# micromouse_schematic.net
KiCad netlist of a schematic drawn in EAGLE
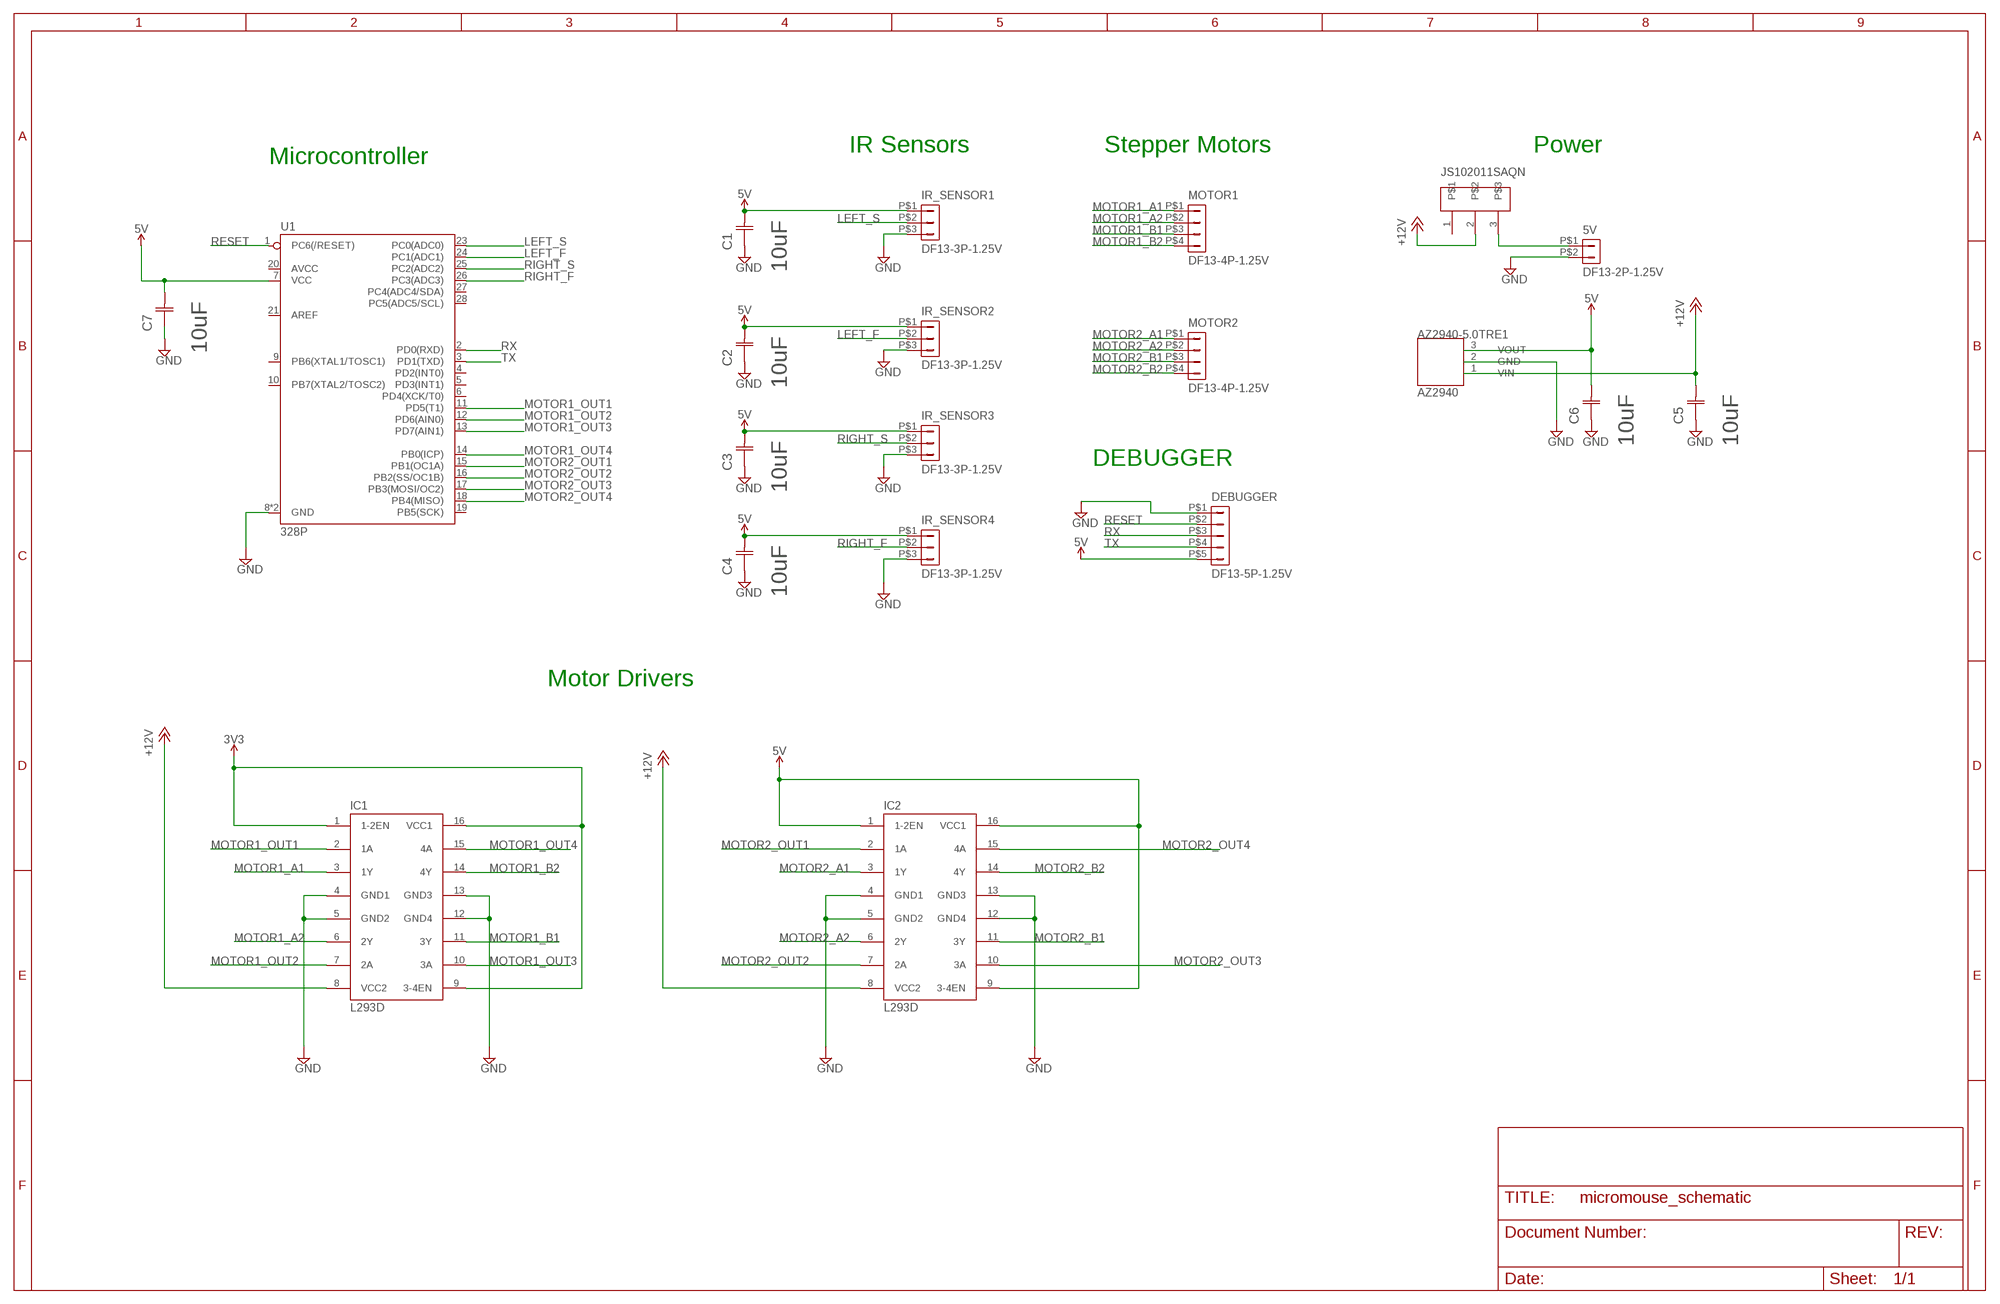
[diagram p0: schematic, sheet 1]

(export (version "E")
  (design (tool "Eeschema 10.0.6"))
  (components
    (comp (ref "5V")
      (value "DF13-2P-1.25V")
      (footprint "eagle-import:DF13C-2P-1.25V")
      (fields (field (name "SPICEPREFIX") "B"))
      (libsource (lib "eagle-import") (part "DF13-2P-1.25V"))
    )
    (comp (ref "AZ2940-5.0TRE1")
      (value "AZ2940")
      (footprint "eagle-import:TO-252")
      (libsource (lib "eagle-import") (part "AZ2940"))
    )
    (comp (ref "C1")
      (value "10uF")
      (footprint "eagle-import:CAPC2013X135N")
      (fields (field (name "MPN") "GRM21BR61C106KE15L") (field (name "TOLERANCE") "±10%"))
      (libsource (lib "eagle-import") (part "GRM21BR61C106KE15L"))
    )
    (comp (ref "C2")
      (value "10uF")
      (footprint "eagle-import:CAPC2013X135N")
      (fields (field (name "MPN") "GRM21BR61C106KE15L") (field (name "TOLERANCE") "±10%"))
      (libsource (lib "eagle-import") (part "GRM21BR61C106KE15L"))
    )
    (comp (ref "C3")
      (value "10uF")
      (footprint "eagle-import:CAPC2013X135N")
      (fields (field (name "MPN") "GRM21BR61C106KE15L") (field (name "TOLERANCE") "±10%"))
      (libsource (lib "eagle-import") (part "GRM21BR61C106KE15L"))
    )
    (comp (ref "C4")
      (value "10uF")
      (footprint "eagle-import:CAPC2013X135N")
      (fields (field (name "MPN") "GRM21BR61C106KE15L") (field (name "TOLERANCE") "±10%"))
      (libsource (lib "eagle-import") (part "GRM21BR61C106KE15L"))
    )
    (comp (ref "C5")
      (value "10uF")
      (footprint "eagle-import:CAPC2013X135N")
      (fields (field (name "MPN") "GRM21BR61C106KE15L") (field (name "TOLERANCE") "±10%"))
      (libsource (lib "eagle-import") (part "GRM21BR61C106KE15L"))
    )
    (comp (ref "C6")
      (value "10uF")
      (footprint "eagle-import:CAPC2013X135N")
      (fields (field (name "MPN") "GRM21BR61C106KE15L") (field (name "TOLERANCE") "±10%"))
      (libsource (lib "eagle-import") (part "GRM21BR61C106KE15L"))
    )
    (comp (ref "C7")
      (value "10uF")
      (footprint "eagle-import:CAPC2013X135N")
      (fields (field (name "MPN") "GRM21BR61C106KE15L") (field (name "TOLERANCE") "±10%"))
      (libsource (lib "eagle-import") (part "GRM21BR61C106KE15L"))
    )
    (comp (ref "DEBUGGER")
      (value "DF13-5P-1.25V")
      (footprint "eagle-import:DF13C-5P-1.25V")
      (libsource (lib "eagle-import") (part "DF13-5P-1.25V"))
    )
    (comp (ref "IC1")
      (value "L293D")
      (footprint "eagle-import:DIL16")
      (libsource (lib "eagle-import") (part "L293D"))
    )
    (comp (ref "IC2")
      (value "L293D")
      (footprint "eagle-import:DIL16")
      (libsource (lib "eagle-import") (part "L293D"))
    )
    (comp (ref "IR_SENSOR1")
      (value "DF13-3P-1.25V")
      (footprint "eagle-import:DF13C-3P-1.25V")
      (libsource (lib "eagle-import") (part "DF13-3P-1.25V"))
    )
    (comp (ref "IR_SENSOR2")
      (value "DF13-3P-1.25V")
      (footprint "eagle-import:DF13C-3P-1.25V")
      (libsource (lib "eagle-import") (part "DF13-3P-1.25V"))
    )
    (comp (ref "IR_SENSOR3")
      (value "DF13-3P-1.25V")
      (footprint "eagle-import:DF13C-3P-1.25V")
      (libsource (lib "eagle-import") (part "DF13-3P-1.25V"))
    )
    (comp (ref "IR_SENSOR4")
      (value "DF13-3P-1.25V")
      (footprint "eagle-import:DF13C-3P-1.25V")
      (libsource (lib "eagle-import") (part "DF13-3P-1.25V"))
    )
    (comp (ref "JS102011SAQN")
      (value "JS102011SAQN")
      (footprint "eagle-import:JS102011SAQN")
      (libsource (lib "eagle-import") (part "JS102011SAQN"))
    )
    (comp (ref "MOTOR1")
      (value "DF13-4P-1.25V")
      (footprint "eagle-import:DF13C-4P-1.25V")
      (libsource (lib "eagle-import") (part "DF13-4P-1.25V"))
    )
    (comp (ref "MOTOR2")
      (value "DF13-4P-1.25V")
      (footprint "eagle-import:DF13C-4P-1.25V")
      (libsource (lib "eagle-import") (part "DF13-4P-1.25V"))
    )
    (comp (ref "U1")
      (value "328P")
      (footprint "eagle-import:DIP28")
      (libsource (lib "eagle-import") (part "ATMEGA328P_PDIP"))
    )
  )
  (nets
    (net (code "1") (name "+12V") (class "Default")
      (node (ref "AZ2940-5.0TRE1") (pin "1") (pinfunction "VIN_1") (pintype "bidirectional"))
      (node (ref "C5") (pin "2") (pinfunction "C2_2") (pintype "passive"))
      (node (ref "IC1") (pin "8") (pinfunction "VCC2_8") (pintype "power_in"))
      (node (ref "IC2") (pin "8") (pinfunction "VCC2_8") (pintype "power_in"))
      (node (ref "JS102011SAQN") (pin "2") (pinfunction "P$2_2") (pintype "bidirectional"))
    )
    (net (code "2") (name "/LEFT_F") (class "Default")
      (node (ref "IR_SENSOR2") (pin "P$2") (pinfunction "2_P$2") (pintype "passive"))
      (node (ref "U1") (pin "24") (pinfunction "PC1(ADC1)_24") (pintype "bidirectional"))
    )
    (net (code "3") (name "/LEFT_S") (class "Default")
      (node (ref "IR_SENSOR1") (pin "P$2") (pinfunction "2_P$2") (pintype "passive"))
      (node (ref "U1") (pin "23") (pinfunction "PC0(ADC0)_23") (pintype "bidirectional"))
    )
    (net (code "4") (name "/MOTOR1_A1") (class "Default")
      (node (ref "IC1") (pin "3") (pinfunction "1Y_3") (pintype "output"))
      (node (ref "MOTOR1") (pin "P$1") (pinfunction "1_P$1") (pintype "passive"))
    )
    (net (code "5") (name "/MOTOR1_A2") (class "Default")
      (node (ref "IC1") (pin "6") (pinfunction "2Y_6") (pintype "output"))
      (node (ref "MOTOR1") (pin "P$2") (pinfunction "2_P$2") (pintype "passive"))
    )
    (net (code "6") (name "/MOTOR1_B1") (class "Default")
      (node (ref "IC1") (pin "11") (pinfunction "3Y_11") (pintype "output"))
      (node (ref "MOTOR1") (pin "P$3") (pinfunction "3_P$3") (pintype "passive"))
    )
    (net (code "7") (name "/MOTOR1_B2") (class "Default")
      (node (ref "IC1") (pin "14") (pinfunction "4Y_14") (pintype "output"))
      (node (ref "MOTOR1") (pin "P$4") (pinfunction "4_P$4") (pintype "passive"))
    )
    (net (code "8") (name "/MOTOR1_OUT1") (class "Default")
      (node (ref "IC1") (pin "2") (pinfunction "1A_2") (pintype "input"))
      (node (ref "U1") (pin "11") (pinfunction "PD5(T1)_11") (pintype "bidirectional"))
    )
    (net (code "9") (name "/MOTOR1_OUT2") (class "Default")
      (node (ref "IC1") (pin "7") (pinfunction "2A_7") (pintype "input"))
      (node (ref "U1") (pin "12") (pinfunction "PD6(AIN0)_12") (pintype "bidirectional"))
    )
    (net (code "10") (name "/MOTOR1_OUT3") (class "Default")
      (node (ref "IC1") (pin "10") (pinfunction "3A_10") (pintype "input"))
      (node (ref "U1") (pin "13") (pinfunction "PD7(AIN1)_13") (pintype "bidirectional"))
    )
    (net (code "11") (name "/MOTOR1_OUT4") (class "Default")
      (node (ref "IC1") (pin "15") (pinfunction "4A_15") (pintype "input"))
      (node (ref "U1") (pin "14") (pinfunction "PB0(ICP)_14") (pintype "bidirectional"))
    )
    (net (code "12") (name "/MOTOR2_A1") (class "Default")
      (node (ref "IC2") (pin "3") (pinfunction "1Y_3") (pintype "output"))
      (node (ref "MOTOR2") (pin "P$1") (pinfunction "1_P$1") (pintype "passive"))
    )
    (net (code "13") (name "/MOTOR2_A2") (class "Default")
      (node (ref "IC2") (pin "6") (pinfunction "2Y_6") (pintype "output"))
      (node (ref "MOTOR2") (pin "P$2") (pinfunction "2_P$2") (pintype "passive"))
    )
    (net (code "14") (name "/MOTOR2_B1") (class "Default")
      (node (ref "IC2") (pin "11") (pinfunction "3Y_11") (pintype "output"))
      (node (ref "MOTOR2") (pin "P$3") (pinfunction "3_P$3") (pintype "passive"))
    )
    (net (code "15") (name "/MOTOR2_B2") (class "Default")
      (node (ref "IC2") (pin "14") (pinfunction "4Y_14") (pintype "output"))
      (node (ref "MOTOR2") (pin "P$4") (pinfunction "4_P$4") (pintype "passive"))
    )
    (net (code "16") (name "/MOTOR2_OUT1") (class "Default")
      (node (ref "IC2") (pin "2") (pinfunction "1A_2") (pintype "input"))
      (node (ref "U1") (pin "15") (pinfunction "PB1(OC1A)_15") (pintype "bidirectional"))
    )
    (net (code "17") (name "/MOTOR2_OUT2") (class "Default")
      (node (ref "IC2") (pin "7") (pinfunction "2A_7") (pintype "input"))
      (node (ref "U1") (pin "16") (pinfunction "PB2(SS/OC1B)_16") (pintype "bidirectional"))
    )
    (net (code "18") (name "/MOTOR2_OUT3") (class "Default")
      (node (ref "IC2") (pin "10") (pinfunction "3A_10") (pintype "input"))
      (node (ref "U1") (pin "17") (pinfunction "PB3(MOSI/OC2)_17") (pintype "bidirectional"))
    )
    (net (code "19") (name "/MOTOR2_OUT4") (class "Default")
      (node (ref "IC2") (pin "15") (pinfunction "4A_15") (pintype "input"))
      (node (ref "U1") (pin "18") (pinfunction "PB4(MISO)_18") (pintype "bidirectional"))
    )
    (net (code "20") (name "/RESET") (class "Default")
      (node (ref "DEBUGGER") (pin "P$2") (pinfunction "2_P$2") (pintype "passive"))
      (node (ref "U1") (pin "1") (pinfunction "PC6(/RESET)_1") (pintype "bidirectional"))
    )
    (net (code "21") (name "/RIGHT_F") (class "Default")
      (node (ref "IR_SENSOR4") (pin "P$2") (pinfunction "2_P$2") (pintype "passive"))
      (node (ref "U1") (pin "26") (pinfunction "PC3(ADC3)_26") (pintype "bidirectional"))
    )
    (net (code "22") (name "/RIGHT_S") (class "Default")
      (node (ref "IR_SENSOR3") (pin "P$2") (pinfunction "2_P$2") (pintype "passive"))
      (node (ref "U1") (pin "25") (pinfunction "PC2(ADC2)_25") (pintype "bidirectional"))
    )
    (net (code "23") (name "/RX") (class "Default")
      (node (ref "DEBUGGER") (pin "P$3") (pinfunction "3_P$3") (pintype "passive"))
      (node (ref "U1") (pin "2") (pinfunction "PD0(RXD)_2") (pintype "bidirectional"))
    )
    (net (code "24") (name "/TX") (class "Default")
      (node (ref "DEBUGGER") (pin "P$4") (pinfunction "4_P$4") (pintype "passive"))
      (node (ref "U1") (pin "3") (pinfunction "PD1(TXD)_3") (pintype "bidirectional"))
    )
    (net (code "25") (name "3V3") (class "Default")
      (node (ref "AZ2940-5.0TRE1") (pin "3") (pinfunction "VOUT_3") (pintype "bidirectional"))
      (node (ref "C1") (pin "2") (pinfunction "C2_2") (pintype "passive"))
      (node (ref "C2") (pin "2") (pinfunction "C2_2") (pintype "passive"))
      (node (ref "C3") (pin "2") (pinfunction "C2_2") (pintype "passive"))
      (node (ref "C4") (pin "2") (pinfunction "C2_2") (pintype "passive"))
      (node (ref "C6") (pin "2") (pinfunction "C2_2") (pintype "passive"))
      (node (ref "C7") (pin "2") (pinfunction "C2_2") (pintype "passive"))
      (node (ref "DEBUGGER") (pin "P$5") (pinfunction "5_P$5") (pintype "passive"))
      (node (ref "IC1") (pin "1") (pinfunction "1-2EN_1") (pintype "input"))
      (node (ref "IC1") (pin "16") (pinfunction "VCC1_16") (pintype "power_in"))
      (node (ref "IC1") (pin "9") (pinfunction "3-4EN_9") (pintype "input"))
      (node (ref "IC2") (pin "1") (pinfunction "1-2EN_1") (pintype "input"))
      (node (ref "IC2") (pin "16") (pinfunction "VCC1_16") (pintype "power_in"))
      (node (ref "IC2") (pin "9") (pinfunction "3-4EN_9") (pintype "input"))
      (node (ref "IR_SENSOR1") (pin "P$1") (pinfunction "1_P$1") (pintype "passive"))
      (node (ref "IR_SENSOR2") (pin "P$1") (pinfunction "1_P$1") (pintype "passive"))
      (node (ref "IR_SENSOR3") (pin "P$1") (pinfunction "1_P$1") (pintype "passive"))
      (node (ref "IR_SENSOR4") (pin "P$1") (pinfunction "1_P$1") (pintype "passive"))
      (node (ref "U1") (pin "7") (pinfunction "VCC_7") (pintype "bidirectional"))
    )
    (net (code "26") (name "GND") (class "Default")
      (node (ref "5V") (pin "P$2") (pinfunction "2_P$2") (pintype "passive"))
      (node (ref "AZ2940-5.0TRE1") (pin "2") (pinfunction "GND_2") (pintype "bidirectional"))
      (node (ref "C1") (pin "1") (pinfunction "C1_1") (pintype "passive"))
      (node (ref "C2") (pin "1") (pinfunction "C1_1") (pintype "passive"))
      (node (ref "C3") (pin "1") (pinfunction "C1_1") (pintype "passive"))
      (node (ref "C4") (pin "1") (pinfunction "C1_1") (pintype "passive"))
      (node (ref "C5") (pin "1") (pinfunction "C1_1") (pintype "passive"))
      (node (ref "C6") (pin "1") (pinfunction "C1_1") (pintype "passive"))
      (node (ref "C7") (pin "1") (pinfunction "C1_1") (pintype "passive"))
      (node (ref "DEBUGGER") (pin "P$1") (pinfunction "1_P$1") (pintype "passive"))
      (node (ref "IC1") (pin "12") (pinfunction "GND4_12") (pintype "power_in"))
      (node (ref "IC1") (pin "13") (pinfunction "GND3_13") (pintype "power_in"))
      (node (ref "IC1") (pin "4") (pinfunction "GND1_4") (pintype "power_in"))
      (node (ref "IC1") (pin "5") (pinfunction "GND2_5") (pintype "power_in"))
      (node (ref "IC2") (pin "12") (pinfunction "GND4_12") (pintype "power_in"))
      (node (ref "IC2") (pin "13") (pinfunction "GND3_13") (pintype "power_in"))
      (node (ref "IC2") (pin "4") (pinfunction "GND1_4") (pintype "power_in"))
      (node (ref "IC2") (pin "5") (pinfunction "GND2_5") (pintype "power_in"))
      (node (ref "IR_SENSOR1") (pin "P$3") (pinfunction "3_P$3") (pintype "passive"))
      (node (ref "IR_SENSOR2") (pin "P$3") (pinfunction "3_P$3") (pintype "passive"))
      (node (ref "IR_SENSOR3") (pin "P$3") (pinfunction "3_P$3") (pintype "passive"))
      (node (ref "IR_SENSOR4") (pin "P$3") (pinfunction "3_P$3") (pintype "passive"))
      (node (ref "U1") (pin "22") (pinfunction "GND_22") (pintype "bidirectional"))
      (node (ref "U1") (pin "8") (pinfunction "GND_8") (pintype "bidirectional"))
    )
    (net (code "27") (name "Net-(5V-1)") (class "Default")
      (node (ref "5V") (pin "P$1") (pinfunction "1_P$1") (pintype "passive"))
      (node (ref "JS102011SAQN") (pin "3") (pinfunction "P$3_3") (pintype "bidirectional"))
    )
    (net (code "28") (name "unconnected-(JS102011SAQN-P$1-Pad1)") (class "Default")
      (node (ref "JS102011SAQN") (pin "1") (pinfunction "P$1_1") (pintype "bidirectional"))
    )
    (net (code "29") (name "unconnected-(U1-AREF-Pad21)") (class "Default")
      (node (ref "U1") (pin "21") (pinfunction "AREF_21") (pintype "bidirectional"))
    )
    (net (code "30") (name "unconnected-(U1-AVCC-Pad20)") (class "Default")
      (node (ref "U1") (pin "20") (pinfunction "AVCC_20") (pintype "bidirectional"))
    )
    (net (code "31") (name "unconnected-(U1-PB5(SCK)-Pad19)") (class "Default")
      (node (ref "U1") (pin "19") (pinfunction "PB5(SCK)_19") (pintype "bidirectional"))
    )
    (net (code "32") (name "unconnected-(U1-PB6(XTAL1{slash}TOSC1)-Pad9)") (class "Default")
      (node (ref "U1") (pin "9") (pinfunction "PB6(XTAL1/TOSC1)_9") (pintype "bidirectional"))
    )
    (net (code "33") (name "unconnected-(U1-PB7(XTAL2{slash}TOSC2)-Pad10)") (class "Default")
      (node (ref "U1") (pin "10") (pinfunction "PB7(XTAL2/TOSC2)_10") (pintype "bidirectional"))
    )
    (net (code "34") (name "unconnected-(U1-PC4(ADC4{slash}SDA)-Pad27)") (class "Default")
      (node (ref "U1") (pin "27") (pinfunction "PC4(ADC4/SDA)_27") (pintype "bidirectional"))
    )
    (net (code "35") (name "unconnected-(U1-PC5(ADC5{slash}SCL)-Pad28)") (class "Default")
      (node (ref "U1") (pin "28") (pinfunction "PC5(ADC5/SCL)_28") (pintype "bidirectional"))
    )
    (net (code "36") (name "unconnected-(U1-PD2(INT0)-Pad4)") (class "Default")
      (node (ref "U1") (pin "4") (pinfunction "PD2(INT0)_4") (pintype "bidirectional"))
    )
    (net (code "37") (name "unconnected-(U1-PD3(INT1)-Pad5)") (class "Default")
      (node (ref "U1") (pin "5") (pinfunction "PD3(INT1)_5") (pintype "bidirectional"))
    )
    (net (code "38") (name "unconnected-(U1-PD4(XCK{slash}T0)-Pad6)") (class "Default")
      (node (ref "U1") (pin "6") (pinfunction "PD4(XCK/T0)_6") (pintype "bidirectional"))
    )
  )
)
